# sensor-small.net
KiCad netlist of a schematic drawn in EAGLE
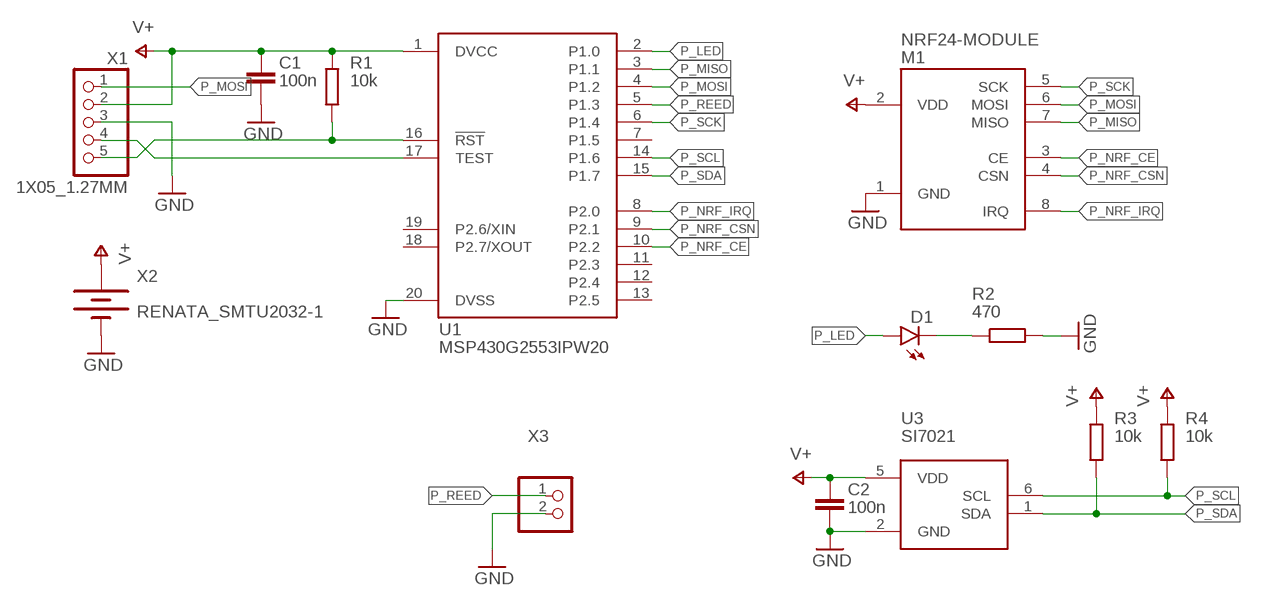
[diagram p0: schematic, sheet 1]

(export (version "E")
  (design (tool "Eeschema 10.0.6"))
  (components
    (comp (ref "C1")
      (value "100n")
      (footprint "eagle-import:C0603")
      (libsource (lib "eagle-import") (part "C0603"))
    )
    (comp (ref "C2")
      (value "100n")
      (footprint "eagle-import:C0603")
      (libsource (lib "eagle-import") (part "C0603"))
    )
    (comp (ref "D1")
      (value "LEDCHIPLED_0805")
      (footprint "eagle-import:CHIPLED_0805")
      (libsource (lib "eagle-import") (part "LEDCHIPLED_0805"))
    )
    (comp (ref "M1")
      (value "NRF24-MODULE")
      (footprint "eagle-import:NRF24-MODULE")
      (libsource (lib "eagle-import") (part "NRF24-MODULE"))
    )
    (comp (ref "R1")
      (value "10k")
      (footprint "eagle-import:R0603")
      (libsource (lib "eagle-import") (part "R0603"))
    )
    (comp (ref "R2")
      (value "470")
      (footprint "eagle-import:R0603")
      (libsource (lib "eagle-import") (part "R0603"))
    )
    (comp (ref "R3")
      (value "10k")
      (footprint "eagle-import:R0603")
      (libsource (lib "eagle-import") (part "R0603"))
    )
    (comp (ref "R4")
      (value "10k")
      (footprint "eagle-import:R0603")
      (libsource (lib "eagle-import") (part "R0603"))
    )
    (comp (ref "U1")
      (value "MSP430G2553IPW20")
      (footprint "eagle-import:PW20")
      (libsource (lib "eagle-import") (part "MSP430G2553IPW20"))
    )
    (comp (ref "U3")
      (value "SI7021")
      (footprint "eagle-import:DFN6-3X3")
      (libsource (lib "eagle-import") (part "SI7021"))
    )
    (comp (ref "X1")
      (value "1X05_1.27MM")
      (footprint "eagle-import:1X05_1.27MM")
      (libsource (lib "eagle-import") (part "1X05_1.27MM"))
    )
    (comp (ref "X2")
      (value "RENATA_SMTU2032-1")
      (footprint "eagle-import:RENATA_SMTU2032-1")
      (libsource (lib "eagle-import") (part "RENATA_SMTU2032-1"))
    )
    (comp (ref "X3")
      (value "PINHD_2_RND")
      (footprint "eagle-import:1X02")
      (libsource (lib "eagle-import") (part "PINHD_2_RND"))
    )
  )
  (nets
    (net (code "1") (name "GND") (class "Default")
      (node (ref "C1") (pin "2") (pinfunction "2_2") (pintype "passive"))
      (node (ref "C2") (pin "2") (pinfunction "2_2") (pintype "passive"))
      (node (ref "M1") (pin "1") (pinfunction "GND_1") (pintype "bidirectional"))
      (node (ref "R2") (pin "2") (pinfunction "2_2") (pintype "passive"))
      (node (ref "U1") (pin "20") (pinfunction "DVSS_20") (pintype "bidirectional"))
      (node (ref "U3") (pin "2") (pinfunction "GND_2") (pintype "power_in"))
      (node (ref "X1") (pin "3") (pinfunction "3_3") (pintype "passive"))
      (node (ref "X2") (pin "2") (pinfunction "-_2") (pintype "power_in"))
      (node (ref "X3") (pin "2") (pinfunction "2_2") (pintype "passive"))
    )
    (net (code "2") (name "Net-(D1-PadC)") (class "Default")
      (node (ref "D1") (pin "C") (pinfunction "C_C") (pintype "passive"))
      (node (ref "R2") (pin "1") (pinfunction "1_1") (pintype "passive"))
    )
    (net (code "3") (name "Net-(U1-TEST)") (class "Default")
      (node (ref "U1") (pin "17") (pinfunction "TEST_17") (pintype "bidirectional"))
      (node (ref "X1") (pin "4") (pinfunction "4_4") (pintype "passive"))
    )
    (net (code "4") (name "Net-(U1-~{RST})") (class "Default")
      (node (ref "R1") (pin "1") (pinfunction "1_1") (pintype "passive"))
      (node (ref "U1") (pin "16") (pinfunction "~{RST}_16") (pintype "bidirectional"))
      (node (ref "X1") (pin "5") (pinfunction "5_5") (pintype "passive"))
    )
    (net (code "5") (name "P_LED") (class "Default")
      (node (ref "D1") (pin "A") (pinfunction "A_A") (pintype "passive"))
      (node (ref "U1") (pin "2") (pinfunction "P1.0_2") (pintype "bidirectional"))
    )
    (net (code "6") (name "P_MISO") (class "Default")
      (node (ref "M1") (pin "7") (pinfunction "MISO_7") (pintype "bidirectional"))
      (node (ref "U1") (pin "3") (pinfunction "P1.1_3") (pintype "bidirectional"))
    )
    (net (code "7") (name "P_MOSI") (class "Default")
      (node (ref "M1") (pin "6") (pinfunction "MOSI_6") (pintype "bidirectional"))
      (node (ref "U1") (pin "4") (pinfunction "P1.2_4") (pintype "bidirectional"))
      (node (ref "X1") (pin "1") (pinfunction "1_1") (pintype "passive"))
    )
    (net (code "8") (name "P_NRF_CE") (class "Default")
      (node (ref "M1") (pin "3") (pinfunction "CE_3") (pintype "bidirectional"))
      (node (ref "U1") (pin "10") (pinfunction "P2.2_10") (pintype "bidirectional"))
    )
    (net (code "9") (name "P_NRF_CSN") (class "Default")
      (node (ref "M1") (pin "4") (pinfunction "CSN_4") (pintype "bidirectional"))
      (node (ref "U1") (pin "9") (pinfunction "P2.1_9") (pintype "bidirectional"))
    )
    (net (code "10") (name "P_NRF_IRQ") (class "Default")
      (node (ref "M1") (pin "8") (pinfunction "IRQ_8") (pintype "bidirectional"))
      (node (ref "U1") (pin "8") (pinfunction "P2.0_8") (pintype "bidirectional"))
    )
    (net (code "11") (name "P_REED") (class "Default")
      (node (ref "U1") (pin "5") (pinfunction "P1.3_5") (pintype "bidirectional"))
      (node (ref "X3") (pin "1") (pinfunction "1_1") (pintype "passive"))
    )
    (net (code "12") (name "P_SCK") (class "Default")
      (node (ref "M1") (pin "5") (pinfunction "SCK_5") (pintype "bidirectional"))
      (node (ref "U1") (pin "6") (pinfunction "P1.4_6") (pintype "bidirectional"))
    )
    (net (code "13") (name "P_SCL") (class "Default")
      (node (ref "R4") (pin "1") (pinfunction "1_1") (pintype "passive"))
      (node (ref "U1") (pin "14") (pinfunction "P1.6_14") (pintype "bidirectional"))
      (node (ref "U3") (pin "6") (pinfunction "SCL_6") (pintype "input"))
    )
    (net (code "14") (name "P_SDA") (class "Default")
      (node (ref "R3") (pin "1") (pinfunction "1_1") (pintype "passive"))
      (node (ref "U1") (pin "15") (pinfunction "P1.7_15") (pintype "bidirectional"))
      (node (ref "U3") (pin "1") (pinfunction "SDA_1") (pintype "input"))
    )
    (net (code "15") (name "V+") (class "Default")
      (node (ref "C1") (pin "1") (pinfunction "1_1") (pintype "passive"))
      (node (ref "C2") (pin "1") (pinfunction "1_1") (pintype "passive"))
      (node (ref "M1") (pin "2") (pinfunction "VDD_2") (pintype "bidirectional"))
      (node (ref "R1") (pin "2") (pinfunction "2_2") (pintype "passive"))
      (node (ref "R3") (pin "2") (pinfunction "2_2") (pintype "passive"))
      (node (ref "R4") (pin "2") (pinfunction "2_2") (pintype "passive"))
      (node (ref "U1") (pin "1") (pinfunction "DVCC_1") (pintype "bidirectional"))
      (node (ref "U3") (pin "5") (pinfunction "VDD_5") (pintype "input"))
      (node (ref "X1") (pin "2") (pinfunction "2_2") (pintype "passive"))
      (node (ref "X2") (pin "1") (pinfunction "+_1") (pintype "power_in"))
    )
    (net (code "16") (name "unconnected-(U1-P1.5-Pad7)") (class "Default")
      (node (ref "U1") (pin "7") (pinfunction "P1.5_7") (pintype "bidirectional"))
    )
    (net (code "17") (name "unconnected-(U1-P2.3-Pad11)") (class "Default")
      (node (ref "U1") (pin "11") (pinfunction "P2.3_11") (pintype "bidirectional"))
    )
    (net (code "18") (name "unconnected-(U1-P2.4-Pad12)") (class "Default")
      (node (ref "U1") (pin "12") (pinfunction "P2.4_12") (pintype "bidirectional"))
    )
    (net (code "19") (name "unconnected-(U1-P2.5-Pad13)") (class "Default")
      (node (ref "U1") (pin "13") (pinfunction "P2.5_13") (pintype "bidirectional"))
    )
    (net (code "20") (name "unconnected-(U1-P2.6{slash}XIN-Pad19)") (class "Default")
      (node (ref "U1") (pin "19") (pinfunction "P2.6/XIN_19") (pintype "bidirectional"))
    )
    (net (code "21") (name "unconnected-(U1-P2.7{slash}XOUT-Pad18)") (class "Default")
      (node (ref "U1") (pin "18") (pinfunction "P2.7/XOUT_18") (pintype "bidirectional"))
    )
  )
)
